# eFuse.net
KiCad netlist of a schematic drawn in Altium Designer
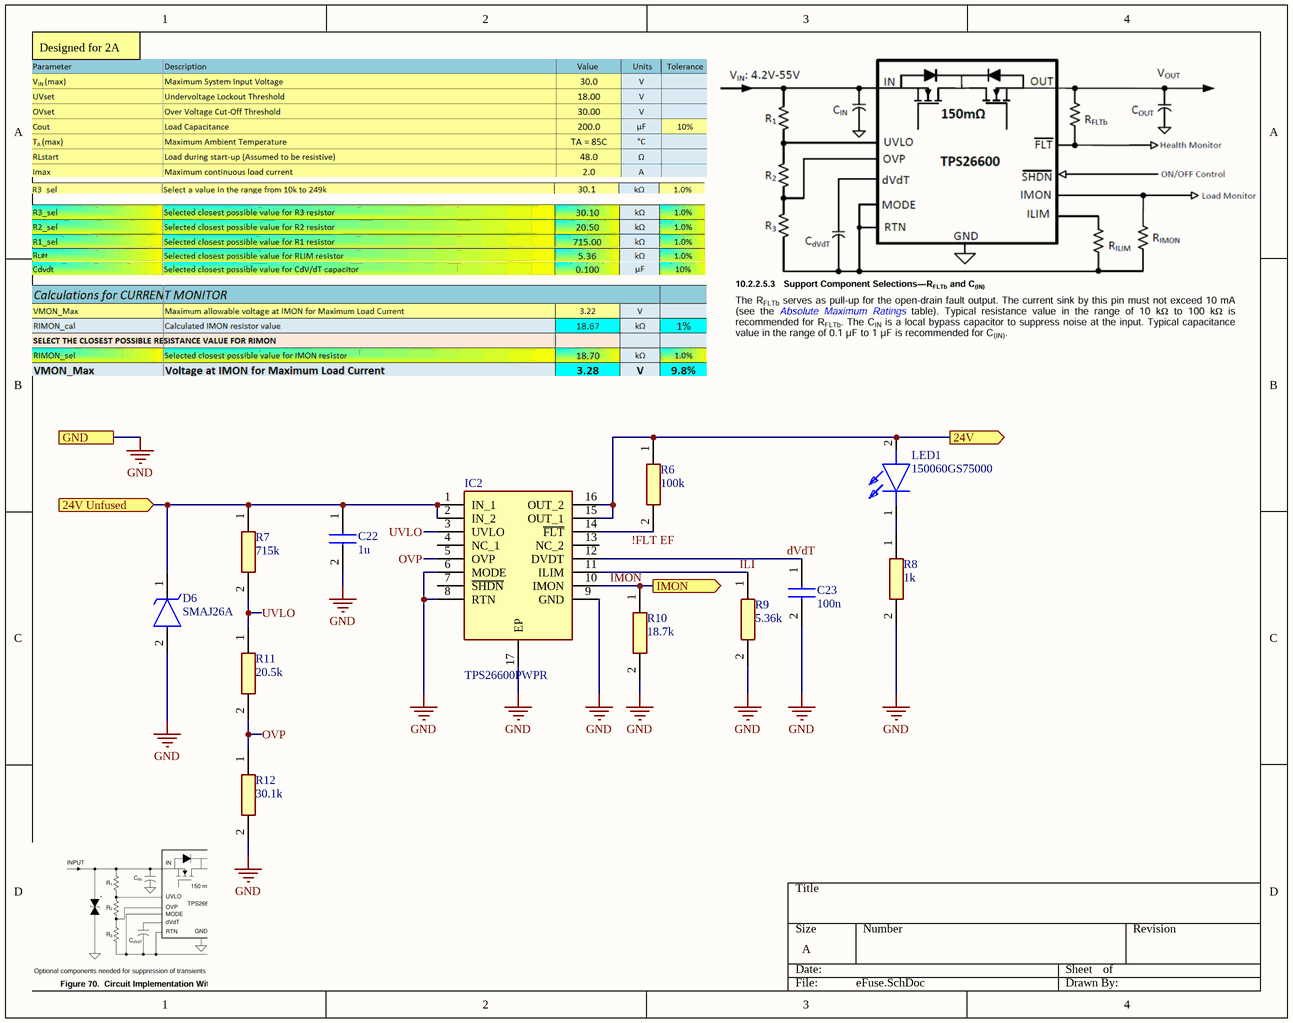
[diagram p0: eFuse.SchDoc]

(export (version "E")
  (design (tool "Eeschema 10.0.6"))
  (components
    (comp (ref "C22")
      (value "1u")
      (footprint "SamacSys:CAPC1608X95N")
      (description "Capacitor")
      (fields
        (field (name "MANUFACTURER_PART_NUMBER") "UMK107AB7105KA-T")
        (field (name "MOUSER PART NUMBER") "963-UMK107AB7105KA-T")
      )
      (libsource (lib "*") (part "UMK107AB7105KA-T"))
    )
    (comp (ref "C23")
      (value "100n")
      (footprint "SamacSys:CAPC1608X90N")
      (description "Capacitor")
      (fields
        (field (name "MANUFACTURER_PART_NUMBER") "06035C104J4Z2A")
        (field (name "MOUSER PART NUMBER") "581-06035C104J4Z2A")
      )
      (libsource (lib "*") (part "06035C104J4Z2A"))
    )
    (comp (ref "D6")
      (value "SMAJ26A")
      (footprint "SamacSys:DIOM5026X229N")
      (description "TVS Diode (Uni-directional)")
      (fields (field (name "MOUSER PART NUMBER") "576-SMAJ26A"))
      (libsource (lib "*") (part "SMAJ26A"))
    )
    (comp (ref "IC2")
      (value "TPS26600PWPR")
      (footprint "SamacSys:SOP65P640X120-17N")
      (description "Integrated Circuit")
      (fields (field (name "MOUSER PART NUMBER") "595-TPS26600PWPR"))
      (libsource (lib "*") (part "TPS26600PWPR"))
    )
    (comp (ref "LED1")
      (value "150060GS75000")
      (footprint "SamacSys:LEDC1608X70N")
      (description "LED")
      (fields (field (name "MOUSER PART NUMBER") "710-150060GS75000"))
      (libsource (lib "*") (part "150060GS75000"))
    )
    (comp (ref "R6")
      (value "100k")
      (footprint "SamacSys:RESC1608X55N")
      (description "Resistor")
      (fields
        (field (name "MANUFACTURER_PART_NUMBER") "CR0603-JW-104ELF")
        (field (name "MOUSER PART NUMBER") "652-CR0603-JW-104ELF")
      )
      (libsource (lib "*") (part "CR0603-JW-104ELF"))
    )
    (comp (ref "R7")
      (value "715k")
      (footprint "SamacSys:RESC1608X55N")
      (description "Resistor")
      (fields
        (field (name "MANUFACTURER_PART_NUMBER") "ERJ-3RED7153V")
        (field (name "MOUSER PART NUMBER") "667-ERJ-3RED7153V")
      )
      (libsource (lib "*") (part "ERJ-3RED7153V"))
    )
    (comp (ref "R8")
      (value "1k")
      (footprint "SamacSys:RESC1608X55N")
      (description "Resistor")
      (fields
        (field (name "MANUFACTURER_PART_NUMBER") "RMCF0603JT1K00")
        (field (name "MOUSER PART NUMBER") "708-RMCF0603JT1K00")
      )
      (libsource (lib "*") (part "RMCF0603JT1K00"))
    )
    (comp (ref "R9")
      (value "5.36k")
      (footprint "SamacSys:RESC1608X55N")
      (description "Resistor")
      (fields
        (field (name "MANUFACTURER_PART_NUMBER") "RK73H1JTTD5361F")
        (field (name "MOUSER PART NUMBER") "660-RK73H1JTTD5361F")
      )
      (libsource (lib "*") (part "RK73H1JTTD5361F"))
    )
    (comp (ref "R10")
      (value "18.7k")
      (footprint "SamacSys:RESC1608X55N")
      (description "Resistor")
      (fields (field (name "MANUFACTURER_PART_NUMBER") "RMCF0603FT18K7"))
      (libsource (lib "*") (part "RMCF0603FT18K7"))
    )
    (comp (ref "R11")
      (value "20.5k")
      (footprint "SamacSys:RESC1608X55N")
      (description "Resistor")
      (fields (field (name "MANUFACTURER_PART_NUMBER") "ERJ-3EKF2052V"))
      (libsource (lib "*") (part "ERJ-3EKF2052V"))
    )
    (comp (ref "R12")
      (value "30.1k")
      (footprint "SamacSys:ERJH3")
      (description "Resistor")
      (fields (field (name "MANUFACTURER_PART_NUMBER") "ERJ-H3EF3012V"))
      (libsource (lib "*") (part "ERJ-H3EF3012V"))
    )
  )
  (nets
    (net (code "1") (name "/!FLT EF") (class "Default")
      (node (ref "IC2") (pin "14") (pinfunction "~{FLT}_14") (pintype "passive"))
      (node (ref "R6") (pin "2") (pinfunction "2_2") (pintype "passive"))
    )
    (net (code "2") (name "/24V") (class "Default")
      (node (ref "IC2") (pin "15") (pinfunction "OUT_1_15") (pintype "passive"))
      (node (ref "IC2") (pin "16") (pinfunction "OUT_2_16") (pintype "passive"))
      (node (ref "LED1") (pin "2") (pinfunction "A_2") (pintype "passive"))
      (node (ref "R6") (pin "1") (pinfunction "1_1") (pintype "passive"))
    )
    (net (code "3") (name "/24V Unfused") (class "Default")
      (node (ref "C22") (pin "1") (pinfunction "1_1") (pintype "passive"))
      (node (ref "D6") (pin "1") (pinfunction "K_1") (pintype "passive"))
      (node (ref "IC2") (pin "1") (pinfunction "IN_1_1") (pintype "passive"))
      (node (ref "IC2") (pin "2") (pinfunction "IN_2_2") (pintype "passive"))
      (node (ref "R7") (pin "1") (pinfunction "1_1") (pintype "passive"))
    )
    (net (code "4") (name "/ILI") (class "Default")
      (node (ref "IC2") (pin "11") (pinfunction "ILIM_11") (pintype "passive"))
      (node (ref "R9") (pin "1") (pinfunction "1_1") (pintype "passive"))
    )
    (net (code "5") (name "/IMON") (class "Default")
      (node (ref "IC2") (pin "10") (pinfunction "IMON_10") (pintype "passive"))
      (node (ref "R10") (pin "1") (pinfunction "1_1") (pintype "passive"))
    )
    (net (code "6") (name "/OVP") (class "Default")
      (node (ref "IC2") (pin "5") (pinfunction "OVP_5") (pintype "passive"))
      (node (ref "R11") (pin "2") (pinfunction "2_2") (pintype "passive"))
      (node (ref "R12") (pin "1") (pinfunction "1_1") (pintype "passive"))
    )
    (net (code "7") (name "/UVLO") (class "Default")
      (node (ref "IC2") (pin "3") (pinfunction "UVLO_3") (pintype "passive"))
      (node (ref "R11") (pin "1") (pinfunction "1_1") (pintype "passive"))
      (node (ref "R7") (pin "2") (pinfunction "2_2") (pintype "passive"))
    )
    (net (code "8") (name "/dVdT") (class "Default")
      (node (ref "C23") (pin "1") (pinfunction "1_1") (pintype "passive"))
      (node (ref "IC2") (pin "12") (pinfunction "DVDT_12") (pintype "passive"))
    )
    (net (code "9") (name "GND") (class "Default")
      (node (ref "C22") (pin "2") (pinfunction "2_2") (pintype "passive"))
      (node (ref "C23") (pin "2") (pinfunction "2_2") (pintype "passive"))
      (node (ref "D6") (pin "2") (pinfunction "A_2") (pintype "passive"))
      (node (ref "IC2") (pin "17") (pinfunction "EP_17") (pintype "passive"))
      (node (ref "IC2") (pin "6") (pinfunction "MODE_6") (pintype "passive"))
      (node (ref "IC2") (pin "8") (pinfunction "RTN_8") (pintype "passive"))
      (node (ref "IC2") (pin "9") (pinfunction "GND_9") (pintype "passive"))
      (node (ref "R10") (pin "2") (pinfunction "2_2") (pintype "passive"))
      (node (ref "R12") (pin "2") (pinfunction "2_2") (pintype "passive"))
      (node (ref "R8") (pin "2") (pinfunction "2_2") (pintype "passive"))
      (node (ref "R9") (pin "2") (pinfunction "2_2") (pintype "passive"))
    )
    (net (code "10") (name "Net-(LED1-K)") (class "Default")
      (node (ref "LED1") (pin "1") (pinfunction "K_1") (pintype "passive"))
      (node (ref "R8") (pin "1") (pinfunction "1_1") (pintype "passive"))
    )
    (net (code "11") (name "unconnected-(IC2-NC_1-Pad4)") (class "Default")
      (node (ref "IC2") (pin "4") (pinfunction "NC_1_4") (pintype "passive"))
    )
    (net (code "12") (name "unconnected-(IC2-NC_2-Pad13)") (class "Default")
      (node (ref "IC2") (pin "13") (pinfunction "NC_2_13") (pintype "passive"))
    )
    (net (code "13") (name "unconnected-(IC2-~{SHDN}-Pad7)") (class "Default")
      (node (ref "IC2") (pin "7") (pinfunction "~{SHDN}_7") (pintype "passive"))
    )
  )
)
